# BOB_v0_6.net
KiCad netlist of a schematic drawn in EAGLE
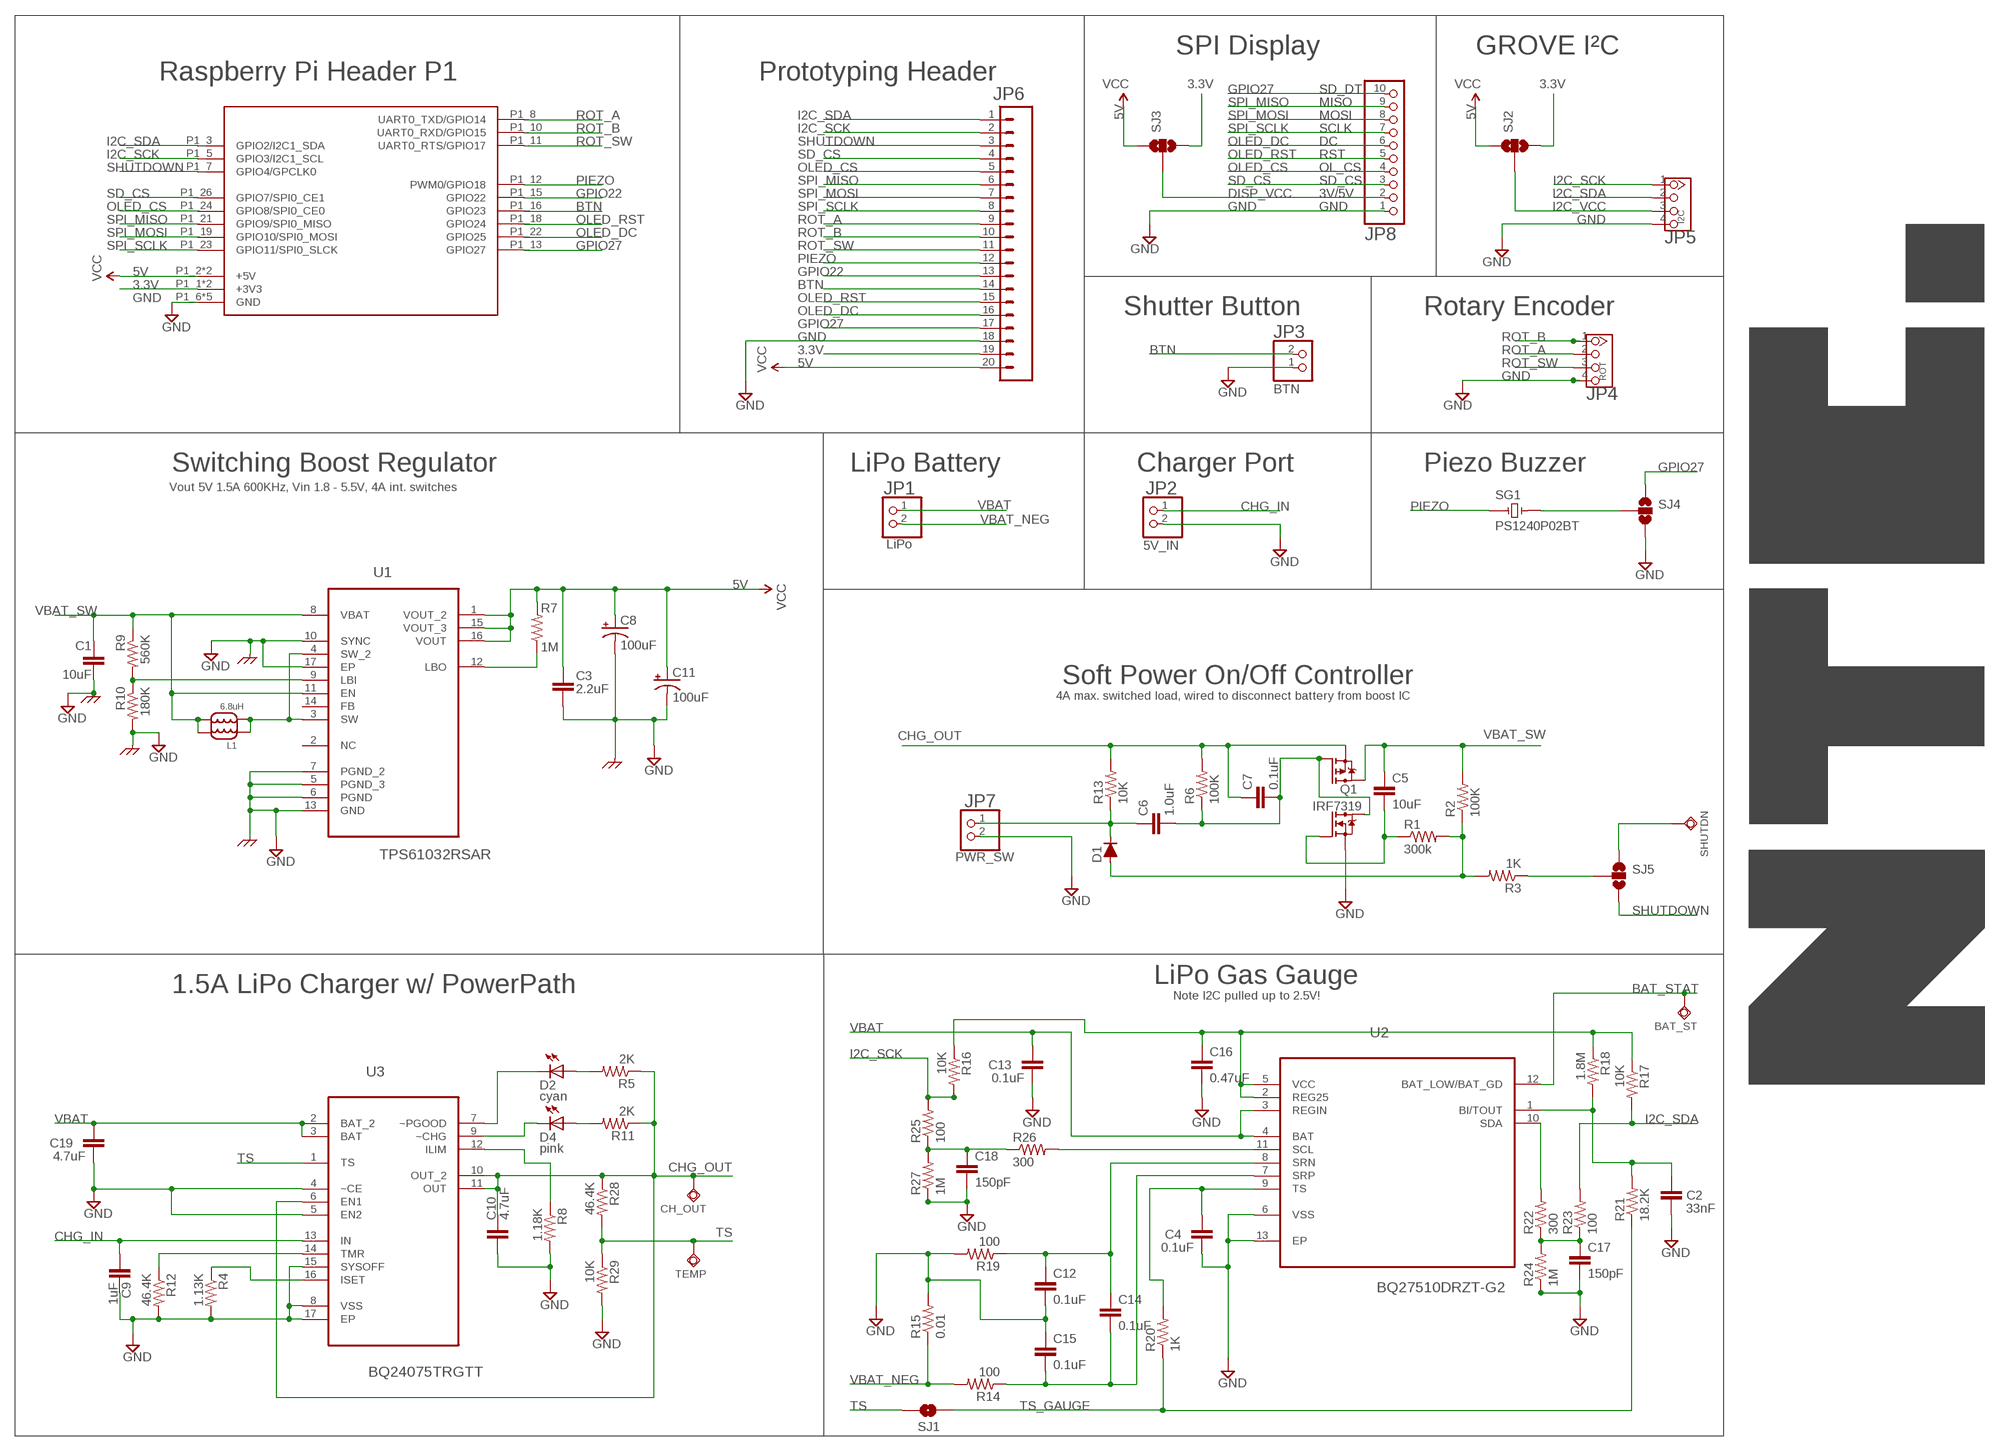
[diagram p0: schematic, sheet 1]

(export (version "E")
  (design (tool "Eeschema 10.0.6"))
  (components
    (comp (ref "BAT_ST")
      (value "TP1.2")
      (footprint "eagle-import:TP_1.2")
      (libsource (lib "eagle-import") (part "TP1.2"))
    )
    (comp (ref "C1")
      (value "10uF")
      (footprint "eagle-import:1206")
      (libsource (lib "eagle-import") (part "CAP1206"))
    )
    (comp (ref "C2")
      (value "33nF")
      (footprint "eagle-import:0603-CAP")
      (libsource (lib "eagle-import") (part "CAP0603-CAP"))
    )
    (comp (ref "C3")
      (value "2.2uF")
      (footprint "eagle-import:0603")
      (libsource (lib "eagle-import") (part "CAP0603"))
    )
    (comp (ref "C4")
      (value "0.1uF")
      (footprint "eagle-import:0603-CAP")
      (libsource (lib "eagle-import") (part "CAP0603-CAP"))
    )
    (comp (ref "C5")
      (value "10uF")
      (footprint "eagle-import:0603-CAP")
      (libsource (lib "eagle-import") (part "10UF-6.3V-20%(0603)"))
    )
    (comp (ref "C6")
      (value "1.0uF")
      (footprint "eagle-import:0603-CAP")
      (libsource (lib "eagle-import") (part "1.0UF-16V-10%(0603)"))
    )
    (comp (ref "C7")
      (value "0.1uF")
      (footprint "eagle-import:0603-CAP")
      (libsource (lib "eagle-import") (part "0.1UF-25V-5%(0603)"))
    )
    (comp (ref "C8")
      (value "100uF")
      (footprint "eagle-import:EIA3216")
      (libsource (lib "eagle-import") (part "CAP_POL1206"))
    )
    (comp (ref "C9")
      (value "1uF")
      (footprint "eagle-import:0603-CAP")
      (libsource (lib "eagle-import") (part "CAP0603-CAP"))
    )
    (comp (ref "C10")
      (value "4.7uF")
      (footprint "eagle-import:0603-CAP")
      (libsource (lib "eagle-import") (part "CAP0603-CAP"))
    )
    (comp (ref "C11")
      (value "100uF")
      (footprint "eagle-import:EIA3216")
      (libsource (lib "eagle-import") (part "CAP_POL1206"))
    )
    (comp (ref "C12")
      (value "0.1uF")
      (footprint "eagle-import:0603-CAP")
      (libsource (lib "eagle-import") (part "SparkFun-Capacitors_CAP0603-CAP"))
    )
    (comp (ref "C13")
      (value "0.1uF")
      (footprint "eagle-import:0603-CAP")
      (libsource (lib "eagle-import") (part "CAP0603-CAP"))
    )
    (comp (ref "C14")
      (value "0.1uF")
      (footprint "eagle-import:0603-CAP")
      (libsource (lib "eagle-import") (part "SparkFun-Capacitors_CAP0603-CAP"))
    )
    (comp (ref "C15")
      (value "0.1uF")
      (footprint "eagle-import:0603-CAP")
      (libsource (lib "eagle-import") (part "SparkFun-Capacitors_CAP0603-CAP"))
    )
    (comp (ref "C16")
      (value "0.47uF")
      (footprint "eagle-import:0603-CAP")
      (libsource (lib "eagle-import") (part "SparkFun-Capacitors_CAP0603-CAP"))
    )
    (comp (ref "C17")
      (value "150pF")
      (footprint "eagle-import:0603-CAP")
      (libsource (lib "eagle-import") (part "SparkFun-Capacitors_CAP0603-CAP"))
    )
    (comp (ref "C18")
      (value "150pF")
      (footprint "eagle-import:0603-CAP")
      (libsource (lib "eagle-import") (part "SparkFun-Capacitors_CAP0603-CAP"))
    )
    (comp (ref "C19")
      (value "4.7uF")
      (footprint "eagle-import:0603-CAP")
      (libsource (lib "eagle-import") (part "CAP0603-CAP"))
    )
    (comp (ref "CH_OUT")
      (value "TP1.2")
      (footprint "eagle-import:TP_1.2")
      (libsource (lib "eagle-import") (part "TP1.2"))
    )
    (comp (ref "D1")
      (value "D-FILL-SMB")
      (footprint "eagle-import:SMB")
      (libsource (lib "eagle-import") (part "D-FILL-SMB"))
    )
    (comp (ref "D2")
      (value "cyan")
      (footprint "eagle-import:LED-0603")
      (libsource (lib "eagle-import") (part "LED0603"))
    )
    (comp (ref "D4")
      (value "pink")
      (footprint "eagle-import:LED-0603")
      (libsource (lib "eagle-import") (part "LED0603"))
    )
    (comp (ref "JP1")
      (value "LiPo")
      (footprint "eagle-import:JST-PH-2-THM")
      (libsource (lib "eagle-import") (part "JST_2PIN-THM"))
    )
    (comp (ref "JP2")
      (value "5V_IN")
      (footprint "eagle-import:JST-PH-2-THM")
      (libsource (lib "eagle-import") (part "JST_2PIN-THM"))
    )
    (comp (ref "JP3")
      (value "BTN")
      (footprint "eagle-import:JST-PH-2-THM")
      (libsource (lib "eagle-import") (part "JST_2PIN-THM"))
    )
    (comp (ref "JP4")
      (value "ROT")
      (footprint "eagle-import:4P-2.0")
      (libsource (lib "eagle-import") (part "TWIG-4P-2.0-2.0"))
    )
    (comp (ref "JP5")
      (value "I2C")
      (footprint "eagle-import:4P-2.0")
      (libsource (lib "eagle-import") (part "TWIG-4P-2.0-2.0"))
    )
    (comp (ref "JP6")
      (value "M20LOCK_LONGPADS")
      (footprint "eagle-import:1X20_LOCK_LONGPADS")
      (libsource (lib "eagle-import") (part "M20LOCK_LONGPADS"))
    )
    (comp (ref "JP7")
      (value "PWR_SW")
      (footprint "eagle-import:JST-PH-2-THM")
      (libsource (lib "eagle-import") (part "JST_2PIN-THM"))
    )
    (comp (ref "JP8")
      (value "PINHD-1X10")
      (footprint "eagle-import:1X10-BIG")
      (libsource (lib "eagle-import") (part "PINHD-1X10"))
    )
    (comp (ref "L1")
      (value "6.8uH")
      (footprint "eagle-import:SUMIDA_CDRH124")
      (libsource (lib "eagle-import") (part "SUMIDA_CDRH124CDRH124NP-6R8MC"))
    )
    (comp (ref "PICAM_SHIELD")
      (value "PICAM_RPI-B-PICAM")
      (footprint "eagle-import:PICAM_RPI-B-PICAM")
      (libsource (lib "eagle-import") (part "PICAM_RPI-B-PICAM"))
    )
    (comp (ref "Q1")
      (value "IRF7319")
      (footprint "eagle-import:SO08-IRF")
      (libsource (lib "eagle-import") (part "IRF7319Q"))
    )
    (comp (ref "R1")
      (value "300k")
      (footprint "eagle-import:0603-RES")
      (libsource (lib "eagle-import") (part "SparkFun-Passives_RESISTOR0603-RES"))
    )
    (comp (ref "R2")
      (value "100K")
      (footprint "eagle-import:0603-RES")
      (libsource (lib "eagle-import") (part "SparkFun-Passives_RESISTOR0603-RES"))
    )
    (comp (ref "R3")
      (value "1K")
      (footprint "eagle-import:0603-RES")
      (libsource (lib "eagle-import") (part "SparkFun-Passives_RESISTOR0603-RES"))
    )
    (comp (ref "R4")
      (value "1.13K")
      (footprint "eagle-import:0603-RES")
      (libsource (lib "eagle-import") (part "RESISTOR0603-RES"))
    )
    (comp (ref "R5")
      (value "2K")
      (footprint "eagle-import:0603-RES")
      (libsource (lib "eagle-import") (part "RESISTOR0603-RES"))
    )
    (comp (ref "R6")
      (value "100K")
      (footprint "eagle-import:0603-RES")
      (libsource (lib "eagle-import") (part "SparkFun-Passives_RESISTOR0603-RES"))
    )
    (comp (ref "R7")
      (value "1M")
      (footprint "eagle-import:0603-RES")
      (libsource (lib "eagle-import") (part "RESISTOR0603-RES"))
    )
    (comp (ref "R8")
      (value "1.18K")
      (footprint "eagle-import:0603-RES")
      (libsource (lib "eagle-import") (part "RESISTOR0603-RES"))
    )
    (comp (ref "R9")
      (value "560K")
      (footprint "eagle-import:0603-RES")
      (libsource (lib "eagle-import") (part "RESISTOR0603-RES"))
    )
    (comp (ref "R10")
      (value "180K")
      (footprint "eagle-import:0603-RES")
      (libsource (lib "eagle-import") (part "RESISTOR0603-RES"))
    )
    (comp (ref "R11")
      (value "2K")
      (footprint "eagle-import:0603-RES")
      (libsource (lib "eagle-import") (part "RESISTOR0603-RES"))
    )
    (comp (ref "R12")
      (value "46.4K")
      (footprint "eagle-import:0603-RES")
      (libsource (lib "eagle-import") (part "RESISTOR0603-RES"))
    )
    (comp (ref "R13")
      (value "10K")
      (footprint "eagle-import:0603-RES")
      (libsource (lib "eagle-import") (part "SparkFun-Passives_RESISTOR0603-RES"))
    )
    (comp (ref "R14")
      (value "100")
      (footprint "eagle-import:0603-RES")
      (libsource (lib "eagle-import") (part "RESISTOR0603-RES"))
    )
    (comp (ref "R15")
      (value "0.01")
      (footprint "eagle-import:0603-RES")
      (libsource (lib "eagle-import") (part "SparkFun-Passives_RESISTOR0603-RES"))
    )
    (comp (ref "R16")
      (value "10K")
      (footprint "eagle-import:0603-RES")
      (libsource (lib "eagle-import") (part "RESISTOR0603-RES"))
    )
    (comp (ref "R17")
      (value "10K")
      (footprint "eagle-import:0603-RES")
      (libsource (lib "eagle-import") (part "RESISTOR0603-RES"))
    )
    (comp (ref "R18")
      (value "1.8M")
      (footprint "eagle-import:0603-RES")
      (libsource (lib "eagle-import") (part "RESISTOR0603-RES"))
    )
    (comp (ref "R19")
      (value "100")
      (footprint "eagle-import:0603-RES")
      (libsource (lib "eagle-import") (part "RESISTOR0603-RES"))
    )
    (comp (ref "R20")
      (value "1K")
      (footprint "eagle-import:0603-RES")
      (libsource (lib "eagle-import") (part "SparkFun-Resistors_RESISTOR0603-RES"))
    )
    (comp (ref "R21")
      (value "18.2K")
      (footprint "eagle-import:0603-RES")
      (libsource (lib "eagle-import") (part "SparkFun-Resistors_RESISTOR0603-RES"))
    )
    (comp (ref "R22")
      (value "300")
      (footprint "eagle-import:0603-RES")
      (libsource (lib "eagle-import") (part "SparkFun-Resistors_RESISTOR0603-RES"))
    )
    (comp (ref "R23")
      (value "100")
      (footprint "eagle-import:0603-RES")
      (libsource (lib "eagle-import") (part "SparkFun-Resistors_RESISTOR0603-RES"))
    )
    (comp (ref "R24")
      (value "1M")
      (footprint "eagle-import:0603-RES")
      (libsource (lib "eagle-import") (part "SparkFun-Resistors_RESISTOR0603-RES"))
    )
    (comp (ref "R25")
      (value "100")
      (footprint "eagle-import:0603-RES")
      (libsource (lib "eagle-import") (part "SparkFun-Resistors_RESISTOR0603-RES"))
    )
    (comp (ref "R26")
      (value "300")
      (footprint "eagle-import:0603-RES")
      (libsource (lib "eagle-import") (part "SparkFun-Resistors_RESISTOR0603-RES"))
    )
    (comp (ref "R27")
      (value "1M")
      (footprint "eagle-import:0603-RES")
      (libsource (lib "eagle-import") (part "SparkFun-Resistors_RESISTOR0603-RES"))
    )
    (comp (ref "R28")
      (value "46.4K")
      (footprint "eagle-import:0603-RES")
      (libsource (lib "eagle-import") (part "RESISTOR0603-RES"))
    )
    (comp (ref "R29")
      (value "10K")
      (footprint "eagle-import:0603-RES")
      (libsource (lib "eagle-import") (part "RESISTOR0603-RES"))
    )
    (comp (ref "SG1")
      (value "PS1240P02BT")
      (footprint "eagle-import:PS1240")
      (libsource (lib "eagle-import") (part "PS1240P02BT"))
    )
    (comp (ref "SHUTDN")
      (value "TP1.2")
      (footprint "eagle-import:TP_1.2")
      (libsource (lib "eagle-import") (part "TP1.2"))
    )
    (comp (ref "SJ1")
      (value "SOLDERJUMPER-OLDTRACE")
      (footprint "eagle-import:SJ_2S-TRACE")
      (libsource (lib "eagle-import") (part "SOLDERJUMPER-OLDTRACE"))
    )
    (comp (ref "SJ2")
      (value "SOLDERJUMPER_2WAYPASTE1&2")
      (footprint "eagle-import:SJ_3_PASTE1&2")
      (libsource (lib "eagle-import") (part "SOLDERJUMPER_2WAYPASTE1&2"))
    )
    (comp (ref "SJ3")
      (value "SOLDERJUMPER_2WAYPASTE2&3")
      (footprint "eagle-import:SJ_3_PASTE2&3")
      (libsource (lib "eagle-import") (part "SOLDERJUMPER_2WAYPASTE2&3"))
    )
    (comp (ref "SJ4")
      (value "SOLDERJUMPER_2WAYPASTE1&2")
      (footprint "eagle-import:SJ_3_PASTE1&2")
      (libsource (lib "eagle-import") (part "SOLDERJUMPER_2WAYPASTE1&2"))
    )
    (comp (ref "SJ5")
      (value "SOLDERJUMPER_2WAYPASTE2&3")
      (footprint "eagle-import:SJ_3_PASTE2&3")
      (libsource (lib "eagle-import") (part "SOLDERJUMPER_2WAYPASTE2&3"))
    )
    (comp (ref "TEMP")
      (value "TP1.2")
      (footprint "eagle-import:TP_1.2")
      (libsource (lib "eagle-import") (part "TP1.2"))
    )
    (comp (ref "U1")
      (value "TPS61032RSAR")
      (footprint "eagle-import:QFN65P400X400X100-17N")
      (libsource (lib "eagle-import") (part "TPS61032RSAR"))
    )
    (comp (ref "U2")
      (value "BQ27510DRZT-G2")
      (footprint "eagle-import:SON40P400X250X100-13N")
      (libsource (lib "eagle-import") (part "BQ27510DRZT-G2"))
    )
    (comp (ref "U3")
      (value "BQ24075TRGTT")
      (footprint "eagle-import:QFN50P300X300X100-17N")
      (libsource (lib "eagle-import") (part "BQ24075TRGTT"))
    )
  )
  (nets
    (net (code "1") (name "3.3V") (class "Default")
      (node (ref "JP6") (pin "19") (pinfunction "19_19") (pintype "passive"))
      (node (ref "PICAM_SHIELD") (pin "P1_1") (pinfunction "+3V3_P1_1") (pintype "power_in"))
      (node (ref "PICAM_SHIELD") (pin "P1_17") (pinfunction "+3V3_P1_17") (pintype "power_in"))
      (node (ref "SJ2") (pin "3") (pinfunction "3_3") (pintype "passive"))
      (node (ref "SJ3") (pin "3") (pinfunction "3_3") (pintype "passive"))
    )
    (net (code "2") (name "5V") (class "Default")
      (node (ref "C11") (pin "A") (pinfunction "+_A") (pintype "passive"))
      (node (ref "C3") (pin "1") (pinfunction "1_1") (pintype "passive"))
      (node (ref "C8") (pin "A") (pinfunction "+_A") (pintype "passive"))
      (node (ref "JP6") (pin "20") (pinfunction "20_20") (pintype "passive"))
      (node (ref "PICAM_SHIELD") (pin "P1_2") (pinfunction "+5V_P1_2") (pintype "power_in"))
      (node (ref "PICAM_SHIELD") (pin "P1_4") (pinfunction "+5V_P1_4") (pintype "power_in"))
      (node (ref "R7") (pin "2") (pinfunction "2_2") (pintype "passive"))
      (node (ref "SJ2") (pin "1") (pinfunction "1_1") (pintype "passive"))
      (node (ref "SJ3") (pin "1") (pinfunction "1_1") (pintype "passive"))
      (node (ref "U1") (pin "1") (pinfunction "VOUT_2_1") (pintype "output"))
      (node (ref "U1") (pin "15") (pinfunction "VOUT_3_15") (pintype "output"))
      (node (ref "U1") (pin "16") (pinfunction "VOUT_16") (pintype "output"))
    )
    (net (code "3") (name "BAT_STAT") (class "Default")
      (node (ref "BAT_ST") (pin "1") (pinfunction "TP_1") (pintype "passive"))
      (node (ref "U2") (pin "12") (pinfunction "BAT_LOW/BAT_GD_12") (pintype "output"))
    )
    (net (code "4") (name "BTN") (class "Default")
      (node (ref "JP3") (pin "2") (pinfunction "1_2") (pintype "passive"))
      (node (ref "JP6") (pin "14") (pinfunction "14_14") (pintype "passive"))
      (node (ref "PICAM_SHIELD") (pin "P1_16") (pinfunction "GPIO23_P1_16") (pintype "bidirectional"))
    )
    (net (code "5") (name "CHG_IN") (class "Default")
      (node (ref "C9") (pin "1") (pinfunction "1_1") (pintype "passive"))
      (node (ref "JP2") (pin "1") (pinfunction "2_1") (pintype "passive"))
      (node (ref "U3") (pin "13") (pinfunction "IN_13") (pintype "input"))
    )
    (net (code "6") (name "CHG_OUT") (class "Default")
      (node (ref "C10") (pin "1") (pinfunction "1_1") (pintype "passive"))
      (node (ref "C7") (pin "1") (pinfunction "1_1") (pintype "passive"))
      (node (ref "CH_OUT") (pin "1") (pinfunction "TP_1") (pintype "passive"))
      (node (ref "Q1") (pin "3") (pinfunction "P-S2_3") (pintype "passive"))
      (node (ref "R11") (pin "1") (pinfunction "1_1") (pintype "passive"))
      (node (ref "R13") (pin "2") (pinfunction "2_2") (pintype "passive"))
      (node (ref "R28") (pin "1") (pinfunction "1_1") (pintype "passive"))
      (node (ref "R5") (pin "1") (pinfunction "1_1") (pintype "passive"))
      (node (ref "R6") (pin "2") (pinfunction "2_2") (pintype "passive"))
      (node (ref "U3") (pin "10") (pinfunction "OUT_2_10") (pintype "output"))
      (node (ref "U3") (pin "11") (pinfunction "OUT_11") (pintype "output"))
      (node (ref "U3") (pin "6") (pinfunction "EN1_6") (pintype "input"))
    )
    (net (code "7") (name "DISP_VCC") (class "Default")
      (node (ref "JP8") (pin "2") (pinfunction "2_2") (pintype "passive"))
      (node (ref "SJ3") (pin "2") (pinfunction "2_2") (pintype "passive"))
    )
    (net (code "8") (name "GND") (class "Default")
      (node (ref "C1") (pin "2") (pinfunction "2_2") (pintype "passive"))
      (node (ref "C10") (pin "2") (pinfunction "2_2") (pintype "passive"))
      (node (ref "C11") (pin "C") (pinfunction "-_C") (pintype "passive"))
      (node (ref "C12") (pin "2") (pinfunction "2_2") (pintype "passive"))
      (node (ref "C13") (pin "2") (pinfunction "2_2") (pintype "passive"))
      (node (ref "C15") (pin "1") (pinfunction "1_1") (pintype "passive"))
      (node (ref "C16") (pin "2") (pinfunction "2_2") (pintype "passive"))
      (node (ref "C17") (pin "2") (pinfunction "2_2") (pintype "passive"))
      (node (ref "C18") (pin "2") (pinfunction "2_2") (pintype "passive"))
      (node (ref "C19") (pin "2") (pinfunction "2_2") (pintype "passive"))
      (node (ref "C2") (pin "2") (pinfunction "2_2") (pintype "passive"))
      (node (ref "C3") (pin "2") (pinfunction "2_2") (pintype "passive"))
      (node (ref "C4") (pin "2") (pinfunction "2_2") (pintype "passive"))
      (node (ref "C8") (pin "C") (pinfunction "-_C") (pintype "passive"))
      (node (ref "C9") (pin "2") (pinfunction "2_2") (pintype "passive"))
      (node (ref "JP2") (pin "2") (pinfunction "1_2") (pintype "passive"))
      (node (ref "JP3") (pin "1") (pinfunction "2_1") (pintype "passive"))
      (node (ref "JP4") (pin "4") (pinfunction "4_4") (pintype "bidirectional"))
      (node (ref "JP5") (pin "4") (pinfunction "4_4") (pintype "bidirectional"))
      (node (ref "JP6") (pin "18") (pinfunction "18_18") (pintype "passive"))
      (node (ref "JP7") (pin "2") (pinfunction "1_2") (pintype "passive"))
      (node (ref "JP8") (pin "1") (pinfunction "1_1") (pintype "passive"))
      (node (ref "PICAM_SHIELD") (pin "P1_14") (pinfunction "GND_P1_14") (pintype "power_in"))
      (node (ref "PICAM_SHIELD") (pin "P1_20") (pinfunction "GND_P1_20") (pintype "power_in"))
      (node (ref "PICAM_SHIELD") (pin "P1_25") (pinfunction "GND_P1_25") (pintype "power_in"))
      (node (ref "PICAM_SHIELD") (pin "P1_6") (pinfunction "GND_P1_6") (pintype "power_in"))
      (node (ref "PICAM_SHIELD") (pin "P1_9") (pinfunction "GND_P1_9") (pintype "power_in"))
      (node (ref "Q1") (pin "1") (pinfunction "N-S1_1") (pintype "passive"))
      (node (ref "R10") (pin "2") (pinfunction "2_2") (pintype "passive"))
      (node (ref "R12") (pin "2") (pinfunction "2_2") (pintype "passive"))
      (node (ref "R15") (pin "2") (pinfunction "2_2") (pintype "passive"))
      (node (ref "R19") (pin "2") (pinfunction "2_2") (pintype "passive"))
      (node (ref "R24") (pin "1") (pinfunction "1_1") (pintype "passive"))
      (node (ref "R27") (pin "1") (pinfunction "1_1") (pintype "passive"))
      (node (ref "R29") (pin "2") (pinfunction "2_2") (pintype "passive"))
      (node (ref "R4") (pin "2") (pinfunction "2_2") (pintype "passive"))
      (node (ref "R8") (pin "2") (pinfunction "2_2") (pintype "passive"))
      (node (ref "SJ4") (pin "3") (pinfunction "3_3") (pintype "passive"))
      (node (ref "U1") (pin "10") (pinfunction "SYNC_10") (pintype "input"))
      (node (ref "U1") (pin "13") (pinfunction "GND_13") (pintype "passive"))
      (node (ref "U1") (pin "17") (pinfunction "EP_17") (pintype "passive"))
      (node (ref "U1") (pin "5") (pinfunction "PGND_3_5") (pintype "passive"))
      (node (ref "U1") (pin "6") (pinfunction "PGND_6") (pintype "passive"))
      (node (ref "U1") (pin "7") (pinfunction "PGND_2_7") (pintype "passive"))
      (node (ref "U2") (pin "13") (pinfunction "EP_13") (pintype "passive"))
      (node (ref "U2") (pin "6") (pinfunction "VSS_6") (pintype "power_in"))
      (node (ref "U3") (pin "15") (pinfunction "SYSOFF_15") (pintype "input"))
      (node (ref "U3") (pin "17") (pinfunction "EP_17") (pintype "passive"))
      (node (ref "U3") (pin "4") (pinfunction "~{CE}_4") (pintype "input"))
      (node (ref "U3") (pin "5") (pinfunction "EN2_5") (pintype "input"))
      (node (ref "U3") (pin "8") (pinfunction "VSS_8") (pintype "passive"))
    )
    (net (code "9") (name "GPIO22") (class "Default")
      (node (ref "JP6") (pin "13") (pinfunction "13_13") (pintype "passive"))
      (node (ref "PICAM_SHIELD") (pin "P1_15") (pinfunction "GPIO22_P1_15") (pintype "bidirectional"))
    )
    (net (code "10") (name "GPIO27") (class "Default")
      (node (ref "JP6") (pin "17") (pinfunction "17_17") (pintype "passive"))
      (node (ref "JP8") (pin "10") (pinfunction "10_10") (pintype "passive"))
      (node (ref "PICAM_SHIELD") (pin "P1_13") (pinfunction "GPIO27_P1_13") (pintype "bidirectional"))
      (node (ref "SJ4") (pin "1") (pinfunction "1_1") (pintype "passive"))
    )
    (net (code "11") (name "I2C_SCK") (class "Default")
      (node (ref "JP5") (pin "1") (pinfunction "1_1") (pintype "bidirectional"))
      (node (ref "JP6") (pin "2") (pinfunction "2_2") (pintype "passive"))
      (node (ref "PICAM_SHIELD") (pin "P1_5") (pinfunction "GPIO3/I2C1_SCL_P1_5") (pintype "bidirectional"))
      (node (ref "R16") (pin "2") (pinfunction "2_2") (pintype "passive"))
      (node (ref "R25") (pin "2") (pinfunction "2_2") (pintype "passive"))
    )
    (net (code "12") (name "I2C_SDA") (class "Default")
      (node (ref "JP5") (pin "2") (pinfunction "2_2") (pintype "bidirectional"))
      (node (ref "JP6") (pin "1") (pinfunction "1_1") (pintype "passive"))
      (node (ref "PICAM_SHIELD") (pin "P1_3") (pinfunction "GPIO2/I2C1_SDA_P1_3") (pintype "bidirectional"))
      (node (ref "R17") (pin "2") (pinfunction "2_2") (pintype "passive"))
      (node (ref "R23") (pin "2") (pinfunction "2_2") (pintype "passive"))
    )
    (net (code "13") (name "I2C_VCC") (class "Default")
      (node (ref "JP5") (pin "3") (pinfunction "3_3") (pintype "bidirectional"))
      (node (ref "SJ2") (pin "2") (pinfunction "2_2") (pintype "passive"))
    )
    (net (code "14") (name "Net-(C17-Pad1)") (class "Default")
      (node (ref "C17") (pin "1") (pinfunction "1_1") (pintype "passive"))
      (node (ref "R22") (pin "1") (pinfunction "1_1") (pintype "passive"))
      (node (ref "R23") (pin "1") (pinfunction "1_1") (pintype "passive"))
      (node (ref "R24") (pin "2") (pinfunction "2_2") (pintype "passive"))
    )
    (net (code "15") (name "Net-(C18-Pad1)") (class "Default")
      (node (ref "C18") (pin "1") (pinfunction "1_1") (pintype "passive"))
      (node (ref "R25") (pin "1") (pinfunction "1_1") (pintype "passive"))
      (node (ref "R26") (pin "1") (pinfunction "1_1") (pintype "passive"))
      (node (ref "R27") (pin "2") (pinfunction "2_2") (pintype "passive"))
    )
    (net (code "16") (name "Net-(D1-A)") (class "Default")
      (node (ref "D1") (pin "2") (pinfunction "A_2") (pintype "passive"))
      (node (ref "R1") (pin "2") (pinfunction "2_2") (pintype "passive"))
      (node (ref "R2") (pin "1") (pinfunction "1_1") (pintype "passive"))
      (node (ref "R3") (pin "2") (pinfunction "2_2") (pintype "passive"))
    )
    (net (code "17") (name "Net-(D1-C)") (class "Default")
      (node (ref "C6") (pin "1") (pinfunction "1_1") (pintype "passive"))
      (node (ref "D1") (pin "1") (pinfunction "C_1") (pintype "passive"))
      (node (ref "JP7") (pin "1") (pinfunction "2_1") (pintype "passive"))
      (node (ref "R13") (pin "1") (pinfunction "1_1") (pintype "passive"))
    )
    (net (code "18") (name "Net-(D2-PadA)") (class "Default")
      (node (ref "D2") (pin "A") (pinfunction "A_A") (pintype "passive"))
      (node (ref "R5") (pin "2") (pinfunction "2_2") (pintype "passive"))
    )
    (net (code "19") (name "Net-(D4-PadA)") (class "Default")
      (node (ref "D4") (pin "A") (pinfunction "A_A") (pintype "passive"))
      (node (ref "R11") (pin "2") (pinfunction "2_2") (pintype "passive"))
    )
    (net (code "20") (name "Net-(Q1-N-G1)") (class "Default")
      (node (ref "C5") (pin "2") (pinfunction "2_2") (pintype "passive"))
      (node (ref "Q1") (pin "2") (pinfunction "N-G1_2") (pintype "passive"))
      (node (ref "R1") (pin "1") (pinfunction "1_1") (pintype "passive"))
    )
    (net (code "21") (name "Net-(Q1-P-G2)") (class "Default")
      (node (ref "C6") (pin "2") (pinfunction "2_2") (pintype "passive"))
      (node (ref "C7") (pin "2") (pinfunction "2_2") (pintype "passive"))
      (node (ref "Q1") (pin "4") (pinfunction "P-G2_4") (pintype "passive"))
      (node (ref "Q1") (pin "7") (pinfunction "N-D1_7") (pintype "passive"))
      (node (ref "Q1") (pin "8") (pinfunction "N-D1_8") (pintype "passive"))
      (node (ref "R6") (pin "1") (pinfunction "1_1") (pintype "passive"))
    )
    (net (code "22") (name "Net-(R3-Pad1)") (class "Default")
      (node (ref "R3") (pin "1") (pinfunction "1_1") (pintype "passive"))
      (node (ref "SJ5") (pin "2") (pinfunction "2_2") (pintype "passive"))
    )
    (net (code "23") (name "Net-(SG1-2)") (class "Default")
      (node (ref "SG1") (pin "P$2") (pinfunction "2_P$2") (pintype "passive"))
      (node (ref "SJ4") (pin "2") (pinfunction "2_2") (pintype "passive"))
    )
    (net (code "24") (name "Net-(SHUTDN-TP)") (class "Default")
      (node (ref "SHUTDN") (pin "1") (pinfunction "TP_1") (pintype "passive"))
      (node (ref "SJ5") (pin "1") (pinfunction "1_1") (pintype "passive"))
    )
    (net (code "25") (name "Net-(U1-LBI)") (class "Default")
      (node (ref "R10") (pin "1") (pinfunction "1_1") (pintype "passive"))
      (node (ref "R9") (pin "2") (pinfunction "2_2") (pintype "passive"))
      (node (ref "U1") (pin "9") (pinfunction "LBI_9") (pintype "input"))
    )
    (net (code "26") (name "Net-(U1-LBO)") (class "Default")
      (node (ref "R7") (pin "1") (pinfunction "1_1") (pintype "passive"))
      (node (ref "U1") (pin "12") (pinfunction "LBO_12") (pintype "output"))
    )
    (net (code "27") (name "Net-(U1-SW)") (class "Default")
      (node (ref "L1") (pin "P$3") (pinfunction "2_P$3") (pintype "passive"))
      (node (ref "L1") (pin "P$4") (pinfunction "2_P$4") (pintype "passive"))
      (node (ref "U1") (pin "3") (pinfunction "SW_3") (pintype "input"))
      (node (ref "U1") (pin "4") (pinfunction "SW_2_4") (pintype "input"))
    )
    (net (code "28") (name "Net-(U2-BI{slash}TOUT)") (class "Default")
      (node (ref "C2") (pin "1") (pinfunction "1_1") (pintype "passive"))
      (node (ref "R18") (pin "2") (pinfunction "2_2") (pintype "passive"))
      (node (ref "R21") (pin "2") (pinfunction "2_2") (pintype "passive"))
      (node (ref "U2") (pin "1") (pinfunction "BI/TOUT_1") (pintype "bidirectional"))
    )
    (net (code "29") (name "Net-(U2-REG25)") (class "Default")
      (node (ref "C16") (pin "1") (pinfunction "1_1") (pintype "passive"))
      (node (ref "R16") (pin "1") (pinfunction "1_1") (pintype "passive"))
      (node (ref "R17") (pin "1") (pinfunction "1_1") (pintype "passive"))
      (node (ref "R18") (pin "1") (pinfunction "1_1") (pintype "passive"))
      (node (ref "U2") (pin "2") (pinfunction "REG25_2") (pintype "power_in"))
      (node (ref "U2") (pin "5") (pinfunction "VCC_5") (pintype "power_in"))
    )
    (net (code "30") (name "Net-(U2-SCL)") (class "Default")
      (node (ref "R26") (pin "2") (pinfunction "2_2") (pintype "passive"))
      (node (ref "U2") (pin "11") (pinfunction "SCL_11") (pintype "input"))
    )
    (net (code "31") (name "Net-(U2-SDA)") (class "Default")
      (node (ref "R22") (pin "2") (pinfunction "2_2") (pintype "passive"))
      (node (ref "U2") (pin "10") (pinfunction "SDA_10") (pintype "bidirectional"))
    )
    (net (code "32") (name "Net-(U2-SRN)") (class "Default")
      (node (ref "C12") (pin "1") (pinfunction "1_1") (pintype "passive"))
      (node (ref "C14") (pin "1") (pinfunction "1_1") (pintype "passive"))
      (node (ref "R19") (pin "1") (pinfunction "1_1") (pintype "passive"))
      (node (ref "U2") (pin "8") (pinfunction "SRN_8") (pintype "input"))
    )
    (net (code "33") (name "Net-(U2-SRP)") (class "Default")
      (node (ref "C14") (pin "2") (pinfunction "2_2") (pintype "passive"))
      (node (ref "C15") (pin "2") (pinfunction "2_2") (pintype "passive"))
      (node (ref "R14") (pin "1") (pinfunction "1_1") (pintype "passive"))
      (node (ref "U2") (pin "7") (pinfunction "SRP_7") (pintype "input"))
    )
    (net (code "34") (name "Net-(U2-TS)") (class "Default")
      (node (ref "C4") (pin "1") (pinfunction "1_1") (pintype "passive"))
      (node (ref "R20") (pin "2") (pinfunction "2_2") (pintype "passive"))
      (node (ref "U2") (pin "9") (pinfunction "TS_9") (pintype "input"))
    )
    (net (code "35") (name "Net-(U3-ILIM)") (class "Default")
      (node (ref "R8") (pin "1") (pinfunction "1_1") (pintype "passive"))
      (node (ref "U3") (pin "12") (pinfunction "ILIM_12") (pintype "output"))
    )
    (net (code "36") (name "Net-(U3-ISET)") (class "Default")
      (node (ref "R4") (pin "1") (pinfunction "1_1") (pintype "passive"))
      (node (ref "U3") (pin "16") (pinfunction "ISET_16") (pintype "bidirectional"))
    )
    (net (code "37") (name "Net-(U3-TMR)") (class "Default")
      (node (ref "R12") (pin "1") (pinfunction "1_1") (pintype "passive"))
      (node (ref "U3") (pin "14") (pinfunction "TMR_14") (pintype "input"))
    )
    (net (code "38") (name "Net-(U3-~{CHG})") (class "Default")
      (node (ref "D4") (pin "C") (pinfunction "C_C") (pintype "passive"))
      (node (ref "U3") (pin "9") (pinfunction "~{CHG}_9") (pintype "output"))
    )
    (net (code "39") (name "Net-(U3-~{PGOOD})") (class "Default")
      (node (ref "D2") (pin "C") (pinfunction "C_C") (pintype "passive"))
      (node (ref "U3") (pin "7") (pinfunction "~{PGOOD}_7") (pintype "output"))
    )
    (net (code "40") (name "OLED_CS") (class "Default")
      (node (ref "JP6") (pin "5") (pinfunction "5_5") (pintype "passive"))
      (node (ref "JP8") (pin "4") (pinfunction "4_4") (pintype "passive"))
      (node (ref "PICAM_SHIELD") (pin "P1_24") (pinfunction "GPIO8/SPI0_CE0_P1_24") (pintype "bidirectional"))
    )
    (net (code "41") (name "OLED_DC") (class "Default")
      (node (ref "JP6") (pin "16") (pinfunction "16_16") (pintype "passive"))
      (node (ref "JP8") (pin "6") (pinfunction "6_6") (pintype "passive"))
      (node (ref "PICAM_SHIELD") (pin "P1_22") (pinfunction "GPIO25_P1_22") (pintype "bidirectional"))
    )
    (net (code "42") (name "OLED_RST") (class "Default")
      (node (ref "JP6") (pin "15") (pinfunction "15_15") (pintype "passive"))
      (node (ref "JP8") (pin "5") (pinfunction "5_5") (pintype "passive"))
      (node (ref "PICAM_SHIELD") (pin "P1_18") (pinfunction "GPIO24_P1_18") (pintype "bidirectional"))
    )
    (net (code "43") (name "PIEZO") (class "Default")
      (node (ref "JP6") (pin "12") (pinfunction "12_12") (pintype "passive"))
      (node (ref "PICAM_SHIELD") (pin "P1_12") (pinfunction "PWM0/GPIO18_P1_12") (pintype "bidirectional"))
      (node (ref "SG1") (pin "P$1") (pinfunction "1_P$1") (pintype "passive"))
    )
    (net (code "44") (name "ROT_A") (class "Default")
      (node (ref "JP4") (pin "2") (pinfunction "2_2") (pintype "bidirectional"))
      (node (ref "JP6") (pin "9") (pinfunction "9_9") (pintype "passive"))
      (node (ref "PICAM_SHIELD") (pin "P1_8") (pinfunction "UART0_TXD/GPIO14_P1_8") (pintype "bidirectional"))
    )
    (net (code "45") (name "ROT_B") (class "Default")
      (node (ref "JP4") (pin "1") (pinfunction "1_1") (pintype "bidirectional"))
      (node (ref "JP6") (pin "10") (pinfunction "10_10") (pintype "passive"))
      (node (ref "PICAM_SHIELD") (pin "P1_10") (pinfunction "UART0_RXD/GPIO15_P1_10") (pintype "bidirectional"))
    )
    (net (code "46") (name "ROT_SW") (class "Default")
      (node (ref "JP4") (pin "3") (pinfunction "3_3") (pintype "bidirectional"))
      (node (ref "JP6") (pin "11") (pinfunction "11_11") (pintype "passive"))
      (node (ref "PICAM_SHIELD") (pin "P1_11") (pinfunction "UART0_RTS/GPIO17_P1_11") (pintype "bidirectional"))
    )
    (net (code "47") (name "SD_CS") (class "Default")
      (node (ref "JP6") (pin "4") (pinfunction "4_4") (pintype "passive"))
      (node (ref "JP8") (pin "3") (pinfunction "3_3") (pintype "passive"))
      (node (ref "PICAM_SHIELD") (pin "P1_26") (pinfunction "GPIO7/SPI0_CE1_P1_26") (pintype "bidirectional"))
    )
    (net (code "48") (name "SHUTDOWN") (class "Default")
      (node (ref "JP6") (pin "3") (pinfunction "3_3") (pintype "passive"))
      (node (ref "PICAM_SHIELD") (pin "P1_7") (pinfunction "GPIO4/GPCLK0_P1_7") (pintype "bidirectional"))
      (node (ref "SJ5") (pin "3") (pinfunction "3_3") (pintype "passive"))
    )
    (net (code "49") (name "SPI_MISO") (class "Default")
      (node (ref "JP6") (pin "6") (pinfunction "6_6") (pintype "passive"))
      (node (ref "JP8") (pin "9") (pinfunction "9_9") (pintype "passive"))
      (node (ref "PICAM_SHIELD") (pin "P1_21") (pinfunction "GPIO9/SPI0_MISO_P1_21") (pintype "bidirectional"))
    )
    (net (code "50") (name "SPI_MOSI") (class "Default")
      (node (ref "JP6") (pin "7") (pinfunction "7_7") (pintype "passive"))
      (node (ref "JP8") (pin "8") (pinfunction "8_8") (pintype "passive"))
      (node (ref "PICAM_SHIELD") (pin "P1_19") (pinfunction "GPIO10/SPI0_MOSI_P1_19") (pintype "bidirectional"))
    )
    (net (code "51") (name "SPI_SCLK") (class "Default")
      (node (ref "JP6") (pin "8") (pinfunction "8_8") (pintype "passive"))
      (node (ref "JP8") (pin "7") (pinfunction "7_7") (pintype "passive"))
      (node (ref "PICAM_SHIELD") (pin "P1_23") (pinfunction "GPIO11/SPI0_SLCK_P1_23") (pintype "bidirectional"))
    )
    (net (code "52") (name "TS") (class "Default")
      (node (ref "R28") (pin "2") (pinfunction "2_2") (pintype "passive"))
      (node (ref "R29") (pin "1") (pinfunction "1_1") (pintype "passive"))
      (node (ref "SJ1") (pin "1") (pinfunction "1_1") (pintype "passive"))
      (node (ref "TEMP") (pin "1") (pinfunction "TP_1") (pintype "passive"))
      (node (ref "U3") (pin "1") (pinfunction "TS_1") (pintype "bidirectional"))
    )
    (net (code "53") (name "TS_GAUGE") (class "Default")
      (node (ref "R20") (pin "1") (pinfunction "1_1") (pintype "passive"))
      (node (ref "R21") (pin "1") (pinfunction "1_1") (pintype "passive"))
      (node (ref "SJ1") (pin "2") (pinfunction "2_2") (pintype "passive"))
    )
    (net (code "54") (name "VBAT") (class "Default")
      (node (ref "C13") (pin "1") (pinfunction "1_1") (pintype "passive"))
      (node (ref "C19") (pin "1") (pinfunction "1_1") (pintype "passive"))
      (node (ref "JP1") (pin "1") (pinfunction "2_1") (pintype "passive"))
      (node (ref "U2") (pin "3") (pinfunction "REGIN_3") (pintype "power_in"))
      (node (ref "U2") (pin "4") (pinfunction "BAT_4") (pintype "input"))
      (node (ref "U3") (pin "2") (pinfunction "BAT_2_2") (pintype "bidirectional"))
      (node (ref "U3") (pin "3") (pinfunction "BAT_3") (pintype "bidirectional"))
    )
    (net (code "55") (name "VBAT_NEG") (class "Default")
      (node (ref "JP1") (pin "2") (pinfunction "1_2") (pintype "passive"))
      (node (ref "R14") (pin "2") (pinfunction "2_2") (pintype "passive"))
      (node (ref "R15") (pin "1") (pinfunction "1_1") (pintype "passive"))
    )
    (net (code "56") (name "VBAT_SW") (class "Default")
      (node (ref "C1") (pin "1") (pinfunction "1_1") (pintype "passive"))
      (node (ref "C5") (pin "1") (pinfunction "1_1") (pintype "passive"))
      (node (ref "L1") (pin "P$1") (pinfunction "1_P$1") (pintype "passive"))
      (node (ref "L1") (pin "P$2") (pinfunction "1_P$2") (pintype "passive"))
      (node (ref "Q1") (pin "5") (pinfunction "P-D2_5") (pintype "passive"))
      (node (ref "Q1") (pin "6") (pinfunction "P-D2_6") (pintype "passive"))
      (node (ref "R2") (pin "2") (pinfunction "2_2") (pintype "passive"))
      (node (ref "R9") (pin "1") (pinfunction "1_1") (pintype "passive"))
      (node (ref "U1") (pin "11") (pinfunction "EN_11") (pintype "input"))
      (node (ref "U1") (pin "8") (pinfunction "VBAT_8") (pintype "input"))
    )
    (net (code "57") (name "unconnected-(U1-FB-Pad14)") (class "Default")
      (node (ref "U1") (pin "14") (pinfunction "FB_14") (pintype "input"))
    )
    (net (code "58") (name "unconnected-(U1-NC-Pad2)") (class "Default")
      (node (ref "U1") (pin "2") (pinfunction "NC_2") (pintype "no_connect"))
    )
  )
)
